# Geiger_Rev1.net
KiCad netlist of a schematic drawn in EAGLE
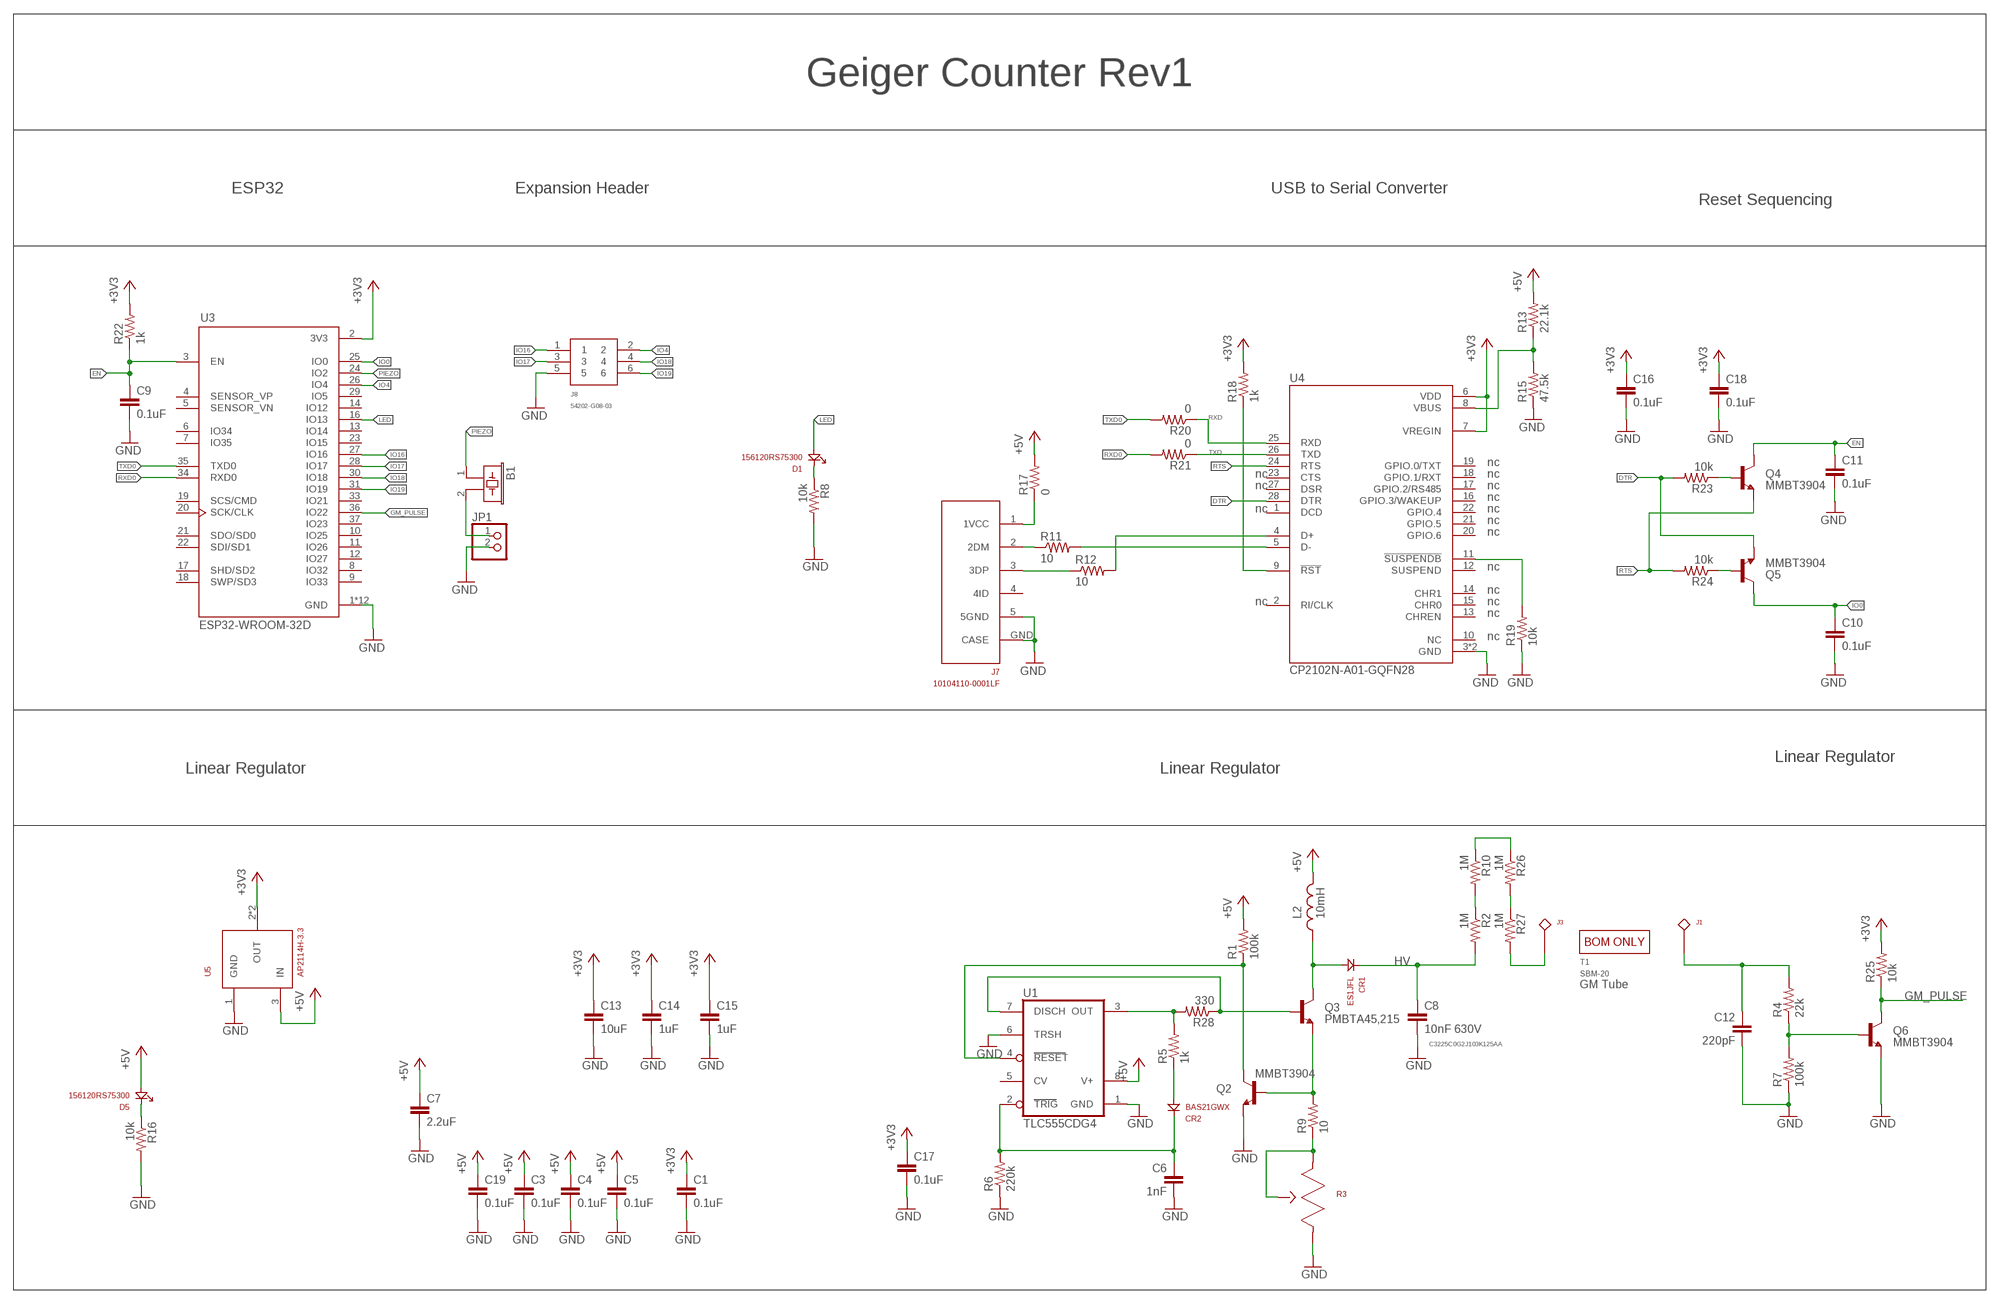
[diagram p0: schematic, sheet 1]

(export (version "E")
  (design (tool "Eeschema 10.0.6"))
  (components
    (comp (ref "B1")
      (value "PIEZO17MM")
      (footprint "eagle-import:PS1740P02E")
      (libsource (lib "eagle-import") (part "PIEZO17MM"))
    )
    (comp (ref "C1")
      (value "0.1uF")
      (footprint "eagle-import:0603")
      (libsource (lib "eagle-import") (part "0603_CAPACITOR"))
    )
    (comp (ref "C3")
      (value "0.1uF")
      (footprint "eagle-import:0603")
      (libsource (lib "eagle-import") (part "0603_CAPACITOR"))
    )
    (comp (ref "C4")
      (value "0.1uF")
      (footprint "eagle-import:0603")
      (libsource (lib "eagle-import") (part "0603_CAPACITOR"))
    )
    (comp (ref "C5")
      (value "0.1uF")
      (footprint "eagle-import:0603")
      (libsource (lib "eagle-import") (part "0603_CAPACITOR"))
    )
    (comp (ref "C6")
      (value "1nF")
      (footprint "eagle-import:0603")
      (libsource (lib "eagle-import") (part "0603_CAPACITOR"))
    )
    (comp (ref "C7")
      (value "2.2uF")
      (footprint "eagle-import:1210")
      (libsource (lib "eagle-import") (part "1210_CAPACITOR"))
    )
    (comp (ref "C8")
      (value "10nF 630V")
      (footprint "eagle-import:1210")
      (libsource (lib "eagle-import") (part "1210_CAPACITOR"))
    )
    (comp (ref "C9")
      (value "0.1uF")
      (footprint "eagle-import:0603")
      (libsource (lib "eagle-import") (part "0603_CAPACITOR"))
    )
    (comp (ref "C10")
      (value "0.1uF")
      (footprint "eagle-import:0603")
      (libsource (lib "eagle-import") (part "0603_CAPACITOR"))
    )
    (comp (ref "C11")
      (value "0.1uF")
      (footprint "eagle-import:0603")
      (libsource (lib "eagle-import") (part "0603_CAPACITOR"))
    )
    (comp (ref "C12")
      (value "220pF")
      (footprint "eagle-import:0603")
      (libsource (lib "eagle-import") (part "0603_CAPACITOR"))
    )
    (comp (ref "C13")
      (value "10uF")
      (footprint "eagle-import:0805")
      (libsource (lib "eagle-import") (part "0805_CAPACITOR"))
    )
    (comp (ref "C14")
      (value "1uF")
      (footprint "eagle-import:0805")
      (libsource (lib "eagle-import") (part "0805_CAPACITOR"))
    )
    (comp (ref "C15")
      (value "1uF")
      (footprint "eagle-import:0805")
      (libsource (lib "eagle-import") (part "0805_CAPACITOR"))
    )
    (comp (ref "C16")
      (value "0.1uF")
      (footprint "eagle-import:0603")
      (libsource (lib "eagle-import") (part "0603_CAPACITOR"))
    )
    (comp (ref "C17")
      (value "0.1uF")
      (footprint "eagle-import:0603")
      (libsource (lib "eagle-import") (part "0603_CAPACITOR"))
    )
    (comp (ref "C18")
      (value "0.1uF")
      (footprint "eagle-import:0603")
      (libsource (lib "eagle-import") (part "0603_CAPACITOR"))
    )
    (comp (ref "C19")
      (value "0.1uF")
      (footprint "eagle-import:0603")
      (libsource (lib "eagle-import") (part "0603_CAPACITOR"))
    )
    (comp (ref "CR1")
      (value "ES1JFL")
      (footprint "eagle-import:SOD123(AK)")
      (fields (field (name "PARTNO") "ES1JFLCT-ND"))
      (libsource (lib "eagle-import") (part "ES1JFL"))
    )
    (comp (ref "CR2")
      (value "BAS21GWX")
      (footprint "eagle-import:SOD123")
      (fields (field (name "PARTNO") "1727-7323-1-ND"))
      (libsource (lib "eagle-import") (part "BAS21GWX"))
    )
    (comp (ref "D1")
      (value "156120RS75300")
      (footprint "eagle-import:1206_REV")
      (fields (field (name "PARTNO") "732-5031-1-ND"))
      (libsource (lib "eagle-import") (part "156120RS75300"))
    )
    (comp (ref "D5")
      (value "156120RS75300")
      (footprint "eagle-import:1206_REV")
      (fields (field (name "PARTNO") "732-5031-1-ND"))
      (libsource (lib "eagle-import") (part "156120RS75300"))
    )
    (comp (ref "J1")
      (value "01010002Z")
      (footprint "eagle-import:01010002Z")
      (fields (field (name "PARTNO") "F4080-ND"))
      (libsource (lib "eagle-import") (part "01010002Z"))
    )
    (comp (ref "J3")
      (value "01010002Z")
      (footprint "eagle-import:01010002Z")
      (fields (field (name "PARTNO") "F4080-ND"))
      (libsource (lib "eagle-import") (part "01010002Z"))
    )
    (comp (ref "J7")
      (value "10104110-0001LF")
      (footprint "eagle-import:MICRO_USB")
      (fields (field (name "PARTNO") "609-4052-1-ND"))
      (libsource (lib "eagle-import") (part "10104110-0001LF"))
    )
    (comp (ref "J8")
      (value "54202-G08-03")
      (footprint "eagle-import:6-SMT-HEADER")
      (fields (field (name "PARTNO") "609-5602-ND"))
      (libsource (lib "eagle-import") (part "54202-G08-03"))
    )
    (comp (ref "JP1")
      (value "PINHD-1X2")
      (footprint "eagle-import:1X02")
      (libsource (lib "eagle-import") (part "PINHD-1X2"))
    )
    (comp (ref "L2")
      (value "10mH")
      (footprint "eagle-import:SDR1005")
      (fields (field (name "PARTNO") "SDR1005-103KLCT-ND"))
      (libsource (lib "eagle-import") (part "SDR1005-103KL"))
    )
    (comp (ref "Q2")
      (value "MMBT3904")
      (footprint "eagle-import:SOT23-3")
      (fields (field (name "PARTNO") "MMBT3904TPMSCT-ND"))
      (libsource (lib "eagle-import") (part "MMBT3904-TP"))
    )
    (comp (ref "Q3")
      (value "PMBTA45,215")
      (footprint "eagle-import:SOT23-3")
      (fields (field (name "PARTNO") "1727-5332-1-ND"))
      (libsource (lib "eagle-import") (part "PMBTA45,215"))
    )
    (comp (ref "Q4")
      (value "MMBT3904")
      (footprint "eagle-import:SOT23-3")
      (fields (field (name "PARTNO") "MMBT3904TPMSCT-ND"))
      (libsource (lib "eagle-import") (part "MMBT3904-TP"))
    )
    (comp (ref "Q5")
      (value "MMBT3904")
      (footprint "eagle-import:SOT23-3")
      (fields (field (name "PARTNO") "MMBT3904TPMSCT-ND"))
      (libsource (lib "eagle-import") (part "MMBT3904-TP"))
    )
    (comp (ref "Q6")
      (value "MMBT3904")
      (footprint "eagle-import:SOT23-3")
      (fields (field (name "PARTNO") "MMBT3904TPMSCT-ND"))
      (libsource (lib "eagle-import") (part "MMBT3904-TP"))
    )
    (comp (ref "R1")
      (value "100k")
      (footprint "eagle-import:0603")
      (libsource (lib "eagle-import") (part "0603_RESISTOR"))
    )
    (comp (ref "R2")
      (value "1M")
      (footprint "eagle-import:0603")
      (libsource (lib "eagle-import") (part "0603_RESISTOR"))
    )
    (comp (ref "R3")
      (value "10")
      (footprint "eagle-import:3361P")
      (fields (field (name "PARTNO") "3361P-1-100GLFCT-ND"))
      (libsource (lib "eagle-import") (part "3361P-1-100GLF"))
    )
    (comp (ref "R4")
      (value "22k")
      (footprint "eagle-import:0603")
      (libsource (lib "eagle-import") (part "0603_RESISTOR"))
    )
    (comp (ref "R5")
      (value "1k")
      (footprint "eagle-import:0603")
      (libsource (lib "eagle-import") (part "0603_RESISTOR"))
    )
    (comp (ref "R6")
      (value "220k")
      (footprint "eagle-import:0603")
      (libsource (lib "eagle-import") (part "0603_RESISTOR"))
    )
    (comp (ref "R7")
      (value "100k")
      (footprint "eagle-import:0603")
      (libsource (lib "eagle-import") (part "0603_RESISTOR"))
    )
    (comp (ref "R8")
      (value "10k")
      (footprint "eagle-import:0603")
      (libsource (lib "eagle-import") (part "0603_RESISTOR"))
    )
    (comp (ref "R9")
      (value "10")
      (footprint "eagle-import:1206")
      (libsource (lib "eagle-import") (part "1206_RESISTOR"))
    )
    (comp (ref "R10")
      (value "1M")
      (footprint "eagle-import:0603")
      (libsource (lib "eagle-import") (part "0603_RESISTOR"))
    )
    (comp (ref "R11")
      (value "10")
      (footprint "eagle-import:0603")
      (libsource (lib "eagle-import") (part "0603_RESISTOR"))
    )
    (comp (ref "R12")
      (value "10")
      (footprint "eagle-import:0603")
      (libsource (lib "eagle-import") (part "0603_RESISTOR"))
    )
    (comp (ref "R13")
      (value "22.1k")
      (footprint "eagle-import:0603")
      (libsource (lib "eagle-import") (part "0603_RESISTOR"))
    )
    (comp (ref "R15")
      (value "47.5k")
      (footprint "eagle-import:0603")
      (libsource (lib "eagle-import") (part "0603_RESISTOR"))
    )
    (comp (ref "R16")
      (value "10k")
      (footprint "eagle-import:0603")
      (libsource (lib "eagle-import") (part "0603_RESISTOR"))
    )
    (comp (ref "R17")
      (value "0")
      (footprint "eagle-import:0603")
      (libsource (lib "eagle-import") (part "0603_RESISTOR"))
    )
    (comp (ref "R18")
      (value "1k")
      (footprint "eagle-import:0603")
      (libsource (lib "eagle-import") (part "0603_RESISTOR"))
    )
    (comp (ref "R19")
      (value "10k")
      (footprint "eagle-import:0603")
      (libsource (lib "eagle-import") (part "0603_RESISTOR"))
    )
    (comp (ref "R20")
      (value "0")
      (footprint "eagle-import:0603")
      (libsource (lib "eagle-import") (part "0603_RESISTOR"))
    )
    (comp (ref "R21")
      (value "0")
      (footprint "eagle-import:0603")
      (libsource (lib "eagle-import") (part "0603_RESISTOR"))
    )
    (comp (ref "R22")
      (value "1k")
      (footprint "eagle-import:0603")
      (libsource (lib "eagle-import") (part "0603_RESISTOR"))
    )
    (comp (ref "R23")
      (value "10k")
      (footprint "eagle-import:0603")
      (libsource (lib "eagle-import") (part "0603_RESISTOR"))
    )
    (comp (ref "R24")
      (value "10k")
      (footprint "eagle-import:0603")
      (libsource (lib "eagle-import") (part "0603_RESISTOR"))
    )
    (comp (ref "R25")
      (value "10k")
      (footprint "eagle-import:0603")
      (libsource (lib "eagle-import") (part "0603_RESISTOR"))
    )
    (comp (ref "R26")
      (value "1M")
      (footprint "eagle-import:0603")
      (libsource (lib "eagle-import") (part "0603_RESISTOR"))
    )
    (comp (ref "R27")
      (value "1M")
      (footprint "eagle-import:0603")
      (libsource (lib "eagle-import") (part "0603_RESISTOR"))
    )
    (comp (ref "R28")
      (value "330")
      (footprint "eagle-import:0603")
      (libsource (lib "eagle-import") (part "0603_RESISTOR"))
    )
    (comp (ref "T1")
      (value "SBM-20")
      (footprint "eagle-import:SBM-20")
      (libsource (lib "eagle-import") (part "SBM-20"))
    )
    (comp (ref "U1")
      (value "TLC555CDG4")
      (footprint "eagle-import:SOIC8")
      (fields (field (name "PARTNO") "296-52992-ND"))
      (libsource (lib "eagle-import") (part "TLC555CDG4"))
    )
    (comp (ref "U3")
      (value "ESP32-WROOM-32D")
      (footprint "eagle-import:MODULE_ESP32-WROOM-32D")
      (fields (field (name "MF") "Espressif Systems"))
      (libsource (lib "eagle-import") (part "ESP32-WROOM-32D"))
    )
    (comp (ref "U4")
      (value "CP2102N-A01-GQFN28")
      (footprint "eagle-import:QFN50P500X500X80-29N")
      (fields (field (name "MF") "Silicon Labs"))
      (libsource (lib "eagle-import") (part "CP2102N-A01-GQFN28"))
    )
    (comp (ref "U5")
      (value "AP2114H-3.3")
      (footprint "eagle-import:SOT223")
      (fields (field (name "PARTNO") "AP2114H-3.3TRG1DICT-ND"))
      (libsource (lib "eagle-import") (part "AP2114H-3.3"))
    )
  )
  (nets
    (net (code "1") (name "+3V3") (class "Default")
      (node (ref "C1") (pin "1") (pinfunction "1_1") (pintype "passive"))
      (node (ref "C13") (pin "1") (pinfunction "1_1") (pintype "passive"))
      (node (ref "C14") (pin "1") (pinfunction "1_1") (pintype "passive"))
      (node (ref "C15") (pin "1") (pinfunction "1_1") (pintype "passive"))
      (node (ref "C16") (pin "1") (pinfunction "1_1") (pintype "passive"))
      (node (ref "C17") (pin "1") (pinfunction "1_1") (pintype "passive"))
      (node (ref "C18") (pin "1") (pinfunction "1_1") (pintype "passive"))
      (node (ref "R18") (pin "2") (pinfunction "2_2") (pintype "passive"))
      (node (ref "R22") (pin "2") (pinfunction "2_2") (pintype "passive"))
      (node (ref "R25") (pin "2") (pinfunction "2_2") (pintype "passive"))
      (node (ref "U3") (pin "2") (pinfunction "3V3_2") (pintype "power_in"))
      (node (ref "U4") (pin "6") (pinfunction "VDD_6") (pintype "power_in"))
      (node (ref "U4") (pin "7") (pinfunction "VREGIN_7") (pintype "power_in"))
      (node (ref "U5") (pin "2") (pinfunction "OUT_2") (pintype "bidirectional"))
      (node (ref "U5") (pin "T") (pinfunction "OUT_T") (pintype "bidirectional"))
    )
    (net (code "2") (name "+5V") (class "Default")
      (node (ref "C19") (pin "1") (pinfunction "1_1") (pintype "passive"))
      (node (ref "C3") (pin "1") (pinfunction "1_1") (pintype "passive"))
      (node (ref "C4") (pin "1") (pinfunction "1_1") (pintype "passive"))
      (node (ref "C5") (pin "1") (pinfunction "1_1") (pintype "passive"))
      (node (ref "C7") (pin "1") (pinfunction "1_1") (pintype "passive"))
      (node (ref "D5") (pin "A") (pinfunction "A_A") (pintype "bidirectional"))
      (node (ref "L2") (pin "P$2") (pinfunction "P$2_P$2") (pintype "bidirectional"))
      (node (ref "R1") (pin "2") (pinfunction "2_2") (pintype "passive"))
      (node (ref "R13") (pin "2") (pinfunction "2_2") (pintype "passive"))
      (node (ref "R17") (pin "2") (pinfunction "2_2") (pintype "passive"))
      (node (ref "U1") (pin "8") (pinfunction "V+_8") (pintype "power_in"))
      (node (ref "U5") (pin "3") (pinfunction "IN_3") (pintype "bidirectional"))
    )
    (net (code "3") (name "/HV") (class "Default")
      (node (ref "C8") (pin "1") (pinfunction "1_1") (pintype "passive"))
      (node (ref "CR1") (pin "K") (pinfunction "K_K") (pintype "bidirectional"))
      (node (ref "R2") (pin "2") (pinfunction "2_2") (pintype "passive"))
    )
    (net (code "4") (name "/RXD") (class "Default")
      (node (ref "R20") (pin "1") (pinfunction "1_1") (pintype "passive"))
      (node (ref "U4") (pin "25") (pinfunction "RXD_25") (pintype "input"))
    )
    (net (code "5") (name "/TXD") (class "Default")
      (node (ref "R21") (pin "1") (pinfunction "1_1") (pintype "passive"))
      (node (ref "U4") (pin "26") (pinfunction "TXD_26") (pintype "output"))
    )
    (net (code "6") (name "DTR") (class "Default")
      (node (ref "Q5") (pin "2") (pinfunction "E_2") (pintype "passive"))
      (node (ref "R23") (pin "2") (pinfunction "2_2") (pintype "passive"))
      (node (ref "U4") (pin "28") (pinfunction "DTR_28") (pintype "output"))
    )
    (net (code "7") (name "EN") (class "Default")
      (node (ref "C11") (pin "1") (pinfunction "1_1") (pintype "passive"))
      (node (ref "C9") (pin "1") (pinfunction "1_1") (pintype "passive"))
      (node (ref "Q4") (pin "3") (pinfunction "C_3") (pintype "passive"))
      (node (ref "R22") (pin "1") (pinfunction "1_1") (pintype "passive"))
      (node (ref "U3") (pin "3") (pinfunction "EN_3") (pintype "input"))
    )
    (net (code "8") (name "GM_PULSE") (class "Default")
      (node (ref "Q6") (pin "3") (pinfunction "C_3") (pintype "passive"))
      (node (ref "R25") (pin "1") (pinfunction "1_1") (pintype "passive"))
      (node (ref "U3") (pin "36") (pinfunction "IO22_36") (pintype "bidirectional"))
    )
    (net (code "9") (name "GND") (class "Default")
      (node (ref "C1") (pin "2") (pinfunction "2_2") (pintype "passive"))
      (node (ref "C10") (pin "2") (pinfunction "2_2") (pintype "passive"))
      (node (ref "C11") (pin "2") (pinfunction "2_2") (pintype "passive"))
      (node (ref "C12") (pin "2") (pinfunction "2_2") (pintype "passive"))
      (node (ref "C13") (pin "2") (pinfunction "2_2") (pintype "passive"))
      (node (ref "C14") (pin "2") (pinfunction "2_2") (pintype "passive"))
      (node (ref "C15") (pin "2") (pinfunction "2_2") (pintype "passive"))
      (node (ref "C16") (pin "2") (pinfunction "2_2") (pintype "passive"))
      (node (ref "C17") (pin "2") (pinfunction "2_2") (pintype "passive"))
      (node (ref "C18") (pin "2") (pinfunction "2_2") (pintype "passive"))
      (node (ref "C19") (pin "2") (pinfunction "2_2") (pintype "passive"))
      (node (ref "C3") (pin "2") (pinfunction "2_2") (pintype "passive"))
      (node (ref "C4") (pin "2") (pinfunction "2_2") (pintype "passive"))
      (node (ref "C5") (pin "2") (pinfunction "2_2") (pintype "passive"))
      (node (ref "C6") (pin "2") (pinfunction "2_2") (pintype "passive"))
      (node (ref "C7") (pin "2") (pinfunction "2_2") (pintype "passive"))
      (node (ref "C8") (pin "2") (pinfunction "2_2") (pintype "passive"))
      (node (ref "C9") (pin "2") (pinfunction "2_2") (pintype "passive"))
      (node (ref "J7") (pin "5") (pinfunction "5GND_5") (pintype "bidirectional"))
      (node (ref "J7") (pin "GND") (pinfunction "CASE_GND") (pintype "bidirectional"))
      (node (ref "J8") (pin "5") (pinfunction "5_5") (pintype "bidirectional"))
      (node (ref "JP1") (pin "2") (pinfunction "2_2") (pintype "passive"))
      (node (ref "Q2") (pin "2") (pinfunction "E_2") (pintype "passive"))
      (node (ref "Q6") (pin "2") (pinfunction "E_2") (pintype "passive"))
      (node (ref "R15") (pin "1") (pinfunction "1_1") (pintype "passive"))
      (node (ref "R16") (pin "2") (pinfunction "2_2") (pintype "passive"))
      (node (ref "R19") (pin "1") (pinfunction "1_1") (pintype "passive"))
      (node (ref "R3") (pin "3") (pinfunction "3_3") (pintype "bidirectional"))
      (node (ref "R6") (pin "1") (pinfunction "1_1") (pintype "passive"))
      (node (ref "R7") (pin "1") (pinfunction "1_1") (pintype "passive"))
      (node (ref "R8") (pin "2") (pinfunction "2_2") (pintype "passive"))
      (node (ref "U1") (pin "1") (pinfunction "GND_1") (pintype "power_in"))
      (node (ref "U1") (pin "6") (pinfunction "TRSH_6") (pintype "input"))
      (node (ref "U3") (pin "1") (pinfunction "GND_1") (pintype "power_in"))
      (node (ref "U3") (pin "15") (pinfunction "GND_15") (pintype "power_in"))
      (node (ref "U3") (pin "38") (pinfunction "GND_38") (pintype "power_in"))
      (node (ref "U3") (pin "39_1") (pinfunction "GND_39_1") (pintype "power_in"))
      (node (ref "U3") (pin "39_2") (pinfunction "GND_39_2") (pintype "power_in"))
      (node (ref "U3") (pin "39_3") (pinfunction "GND_39_3") (pintype "power_in"))
      (node (ref "U3") (pin "39_4") (pinfunction "GND_39_4") (pintype "power_in"))
      (node (ref "U3") (pin "39_5") (pinfunction "GND_39_5") (pintype "power_in"))
      (node (ref "U3") (pin "39_6") (pinfunction "GND_39_6") (pintype "power_in"))
      (node (ref "U3") (pin "39_7") (pinfunction "GND_39_7") (pintype "power_in"))
      (node (ref "U3") (pin "39_8") (pinfunction "GND_39_8") (pintype "power_in"))
      (node (ref "U3") (pin "39_9") (pinfunction "GND_39_9") (pintype "power_in"))
      (node (ref "U4") (pin "29") (pinfunction "GND_29") (pintype "power_in"))
      (node (ref "U4") (pin "3") (pinfunction "GND_3") (pintype "power_in"))
      (node (ref "U5") (pin "1") (pinfunction "GND_1") (pintype "bidirectional"))
    )
    (net (code "10") (name "IO0") (class "Default")
      (node (ref "C10") (pin "1") (pinfunction "1_1") (pintype "passive"))
      (node (ref "Q5") (pin "3") (pinfunction "C_3") (pintype "passive"))
      (node (ref "U3") (pin "25") (pinfunction "IO0_25") (pintype "bidirectional"))
    )
    (net (code "11") (name "IO4") (class "Default")
      (node (ref "J8") (pin "2") (pinfunction "2_2") (pintype "bidirectional"))
      (node (ref "U3") (pin "26") (pinfunction "IO4_26") (pintype "bidirectional"))
    )
    (net (code "12") (name "IO16") (class "Default")
      (node (ref "J8") (pin "1") (pinfunction "1_1") (pintype "bidirectional"))
      (node (ref "U3") (pin "27") (pinfunction "IO16_27") (pintype "bidirectional"))
    )
    (net (code "13") (name "IO17") (class "Default")
      (node (ref "J8") (pin "3") (pinfunction "3_3") (pintype "bidirectional"))
      (node (ref "U3") (pin "28") (pinfunction "IO17_28") (pintype "bidirectional"))
    )
    (net (code "14") (name "IO18") (class "Default")
      (node (ref "J8") (pin "4") (pinfunction "4_4") (pintype "bidirectional"))
      (node (ref "U3") (pin "30") (pinfunction "IO18_30") (pintype "bidirectional"))
    )
    (net (code "15") (name "IO19") (class "Default")
      (node (ref "J8") (pin "6") (pinfunction "6_6") (pintype "bidirectional"))
      (node (ref "U3") (pin "31") (pinfunction "IO19_31") (pintype "bidirectional"))
    )
    (net (code "16") (name "LED") (class "Default")
      (node (ref "D1") (pin "A") (pinfunction "A_A") (pintype "bidirectional"))
      (node (ref "U3") (pin "16") (pinfunction "IO13_16") (pintype "bidirectional"))
    )
    (net (code "17") (name "Net-(B1-Pad2)") (class "Default")
      (node (ref "B1") (pin "2") (pinfunction "2_2") (pintype "passive"))
      (node (ref "JP1") (pin "1") (pinfunction "1_1") (pintype "passive"))
    )
    (net (code "18") (name "Net-(C12-Pad1)") (class "Default")
      (node (ref "C12") (pin "1") (pinfunction "1_1") (pintype "passive"))
      (node (ref "J1") (pin "P$1") (pinfunction "P$1_P$1") (pintype "bidirectional"))
      (node (ref "R4") (pin "2") (pinfunction "2_2") (pintype "passive"))
    )
    (net (code "19") (name "Net-(CR2-A)") (class "Default")
      (node (ref "CR2") (pin "2") (pinfunction "A_2") (pintype "bidirectional"))
      (node (ref "R5") (pin "1") (pinfunction "1_1") (pintype "passive"))
    )
    (net (code "20") (name "Net-(CR2-K)") (class "Default")
      (node (ref "C6") (pin "1") (pinfunction "1_1") (pintype "passive"))
      (node (ref "CR2") (pin "1") (pinfunction "K_1") (pintype "bidirectional"))
      (node (ref "R6") (pin "2") (pinfunction "2_2") (pintype "passive"))
      (node (ref "U1") (pin "2") (pinfunction "TRIG_2") (pintype "bidirectional"))
    )
    (net (code "21") (name "Net-(D1-PadK)") (class "Default")
      (node (ref "D1") (pin "K") (pinfunction "K_K") (pintype "bidirectional"))
      (node (ref "R8") (pin "1") (pinfunction "1_1") (pintype "passive"))
    )
    (net (code "22") (name "Net-(D5-PadK)") (class "Default")
      (node (ref "D5") (pin "K") (pinfunction "K_K") (pintype "bidirectional"))
      (node (ref "R16") (pin "1") (pinfunction "1_1") (pintype "passive"))
    )
    (net (code "23") (name "Net-(J3-PadP$1)") (class "Default")
      (node (ref "J3") (pin "P$1") (pinfunction "P$1_P$1") (pintype "bidirectional"))
      (node (ref "R27") (pin "2") (pinfunction "2_2") (pintype "passive"))
    )
    (net (code "24") (name "Net-(J7-1VCC)") (class "Default")
      (node (ref "J7") (pin "1") (pinfunction "1VCC_1") (pintype "bidirectional"))
      (node (ref "R17") (pin "1") (pinfunction "1_1") (pintype "passive"))
    )
    (net (code "25") (name "Net-(J7-2DM)") (class "Default")
      (node (ref "J7") (pin "2") (pinfunction "2DM_2") (pintype "bidirectional"))
      (node (ref "R11") (pin "1") (pinfunction "1_1") (pintype "passive"))
    )
    (net (code "26") (name "Net-(J7-3DP)") (class "Default")
      (node (ref "J7") (pin "3") (pinfunction "3DP_3") (pintype "bidirectional"))
      (node (ref "R12") (pin "1") (pinfunction "1_1") (pintype "passive"))
    )
    (net (code "27") (name "Net-(Q2-B)") (class "Default")
      (node (ref "Q2") (pin "1") (pinfunction "B_1") (pintype "passive"))
      (node (ref "Q3") (pin "2") (pinfunction "E_2") (pintype "passive"))
      (node (ref "R9") (pin "2") (pinfunction "2_2") (pintype "passive"))
    )
    (net (code "28") (name "Net-(Q2-C)") (class "Default")
      (node (ref "Q2") (pin "3") (pinfunction "C_3") (pintype "passive"))
      (node (ref "R1") (pin "1") (pinfunction "1_1") (pintype "passive"))
      (node (ref "U1") (pin "4") (pinfunction "RESET_4") (pintype "input"))
    )
    (net (code "29") (name "Net-(Q3-B)") (class "Default")
      (node (ref "Q3") (pin "1") (pinfunction "B_1") (pintype "passive"))
      (node (ref "R28") (pin "1") (pinfunction "1_1") (pintype "passive"))
      (node (ref "U1") (pin "7") (pinfunction "DISCH_7") (pintype "input"))
    )
    (net (code "30") (name "Net-(Q3-C)") (class "Default")
      (node (ref "CR1") (pin "A") (pinfunction "A_A") (pintype "bidirectional"))
      (node (ref "L2") (pin "P$1") (pinfunction "P$1_P$1") (pintype "bidirectional"))
      (node (ref "Q3") (pin "3") (pinfunction "C_3") (pintype "passive"))
    )
    (net (code "31") (name "Net-(Q4-B)") (class "Default")
      (node (ref "Q4") (pin "1") (pinfunction "B_1") (pintype "passive"))
      (node (ref "R23") (pin "1") (pinfunction "1_1") (pintype "passive"))
    )
    (net (code "32") (name "Net-(Q5-B)") (class "Default")
      (node (ref "Q5") (pin "1") (pinfunction "B_1") (pintype "passive"))
      (node (ref "R24") (pin "1") (pinfunction "1_1") (pintype "passive"))
    )
    (net (code "33") (name "Net-(Q6-B)") (class "Default")
      (node (ref "Q6") (pin "1") (pinfunction "B_1") (pintype "passive"))
      (node (ref "R4") (pin "1") (pinfunction "1_1") (pintype "passive"))
      (node (ref "R7") (pin "2") (pinfunction "2_2") (pintype "passive"))
    )
    (net (code "34") (name "Net-(R3-Pad1)") (class "Default")
      (node (ref "R3") (pin "1") (pinfunction "1_1") (pintype "bidirectional"))
      (node (ref "R3") (pin "2") (pinfunction "2_2") (pintype "bidirectional"))
      (node (ref "R9") (pin "1") (pinfunction "1_1") (pintype "passive"))
    )
    (net (code "35") (name "Net-(R10-Pad1)") (class "Default")
      (node (ref "R10") (pin "1") (pinfunction "1_1") (pintype "passive"))
      (node (ref "R26") (pin "1") (pinfunction "1_1") (pintype "passive"))
    )
    (net (code "36") (name "Net-(R10-Pad2)") (class "Default")
      (node (ref "R10") (pin "2") (pinfunction "2_2") (pintype "passive"))
      (node (ref "R2") (pin "1") (pinfunction "1_1") (pintype "passive"))
    )
    (net (code "37") (name "Net-(R26-Pad2)") (class "Default")
      (node (ref "R26") (pin "2") (pinfunction "2_2") (pintype "passive"))
      (node (ref "R27") (pin "1") (pinfunction "1_1") (pintype "passive"))
    )
    (net (code "38") (name "Net-(U1-OUT)") (class "Default")
      (node (ref "R28") (pin "2") (pinfunction "2_2") (pintype "passive"))
      (node (ref "R5") (pin "2") (pinfunction "2_2") (pintype "passive"))
      (node (ref "U1") (pin "3") (pinfunction "OUT_3") (pintype "output"))
    )
    (net (code "39") (name "Net-(U4-D+)") (class "Default")
      (node (ref "R12") (pin "2") (pinfunction "2_2") (pintype "passive"))
      (node (ref "U4") (pin "4") (pinfunction "D+_4") (pintype "bidirectional"))
    )
    (net (code "40") (name "Net-(U4-D-)") (class "Default")
      (node (ref "R11") (pin "2") (pinfunction "2_2") (pintype "passive"))
      (node (ref "U4") (pin "5") (pinfunction "D-_5") (pintype "bidirectional"))
    )
    (net (code "41") (name "Net-(U4-VBUS)") (class "Default")
      (node (ref "R13") (pin "1") (pinfunction "1_1") (pintype "passive"))
      (node (ref "R15") (pin "2") (pinfunction "2_2") (pintype "passive"))
      (node (ref "U4") (pin "8") (pinfunction "VBUS_8") (pintype "power_in"))
    )
    (net (code "42") (name "Net-(U4-~{RST})") (class "Default")
      (node (ref "R18") (pin "1") (pinfunction "1_1") (pintype "passive"))
      (node (ref "U4") (pin "9") (pinfunction "~{RST}_9") (pintype "input"))
    )
    (net (code "43") (name "Net-(U4-~{SUSPENDB})") (class "Default")
      (node (ref "R19") (pin "2") (pinfunction "2_2") (pintype "passive"))
      (node (ref "U4") (pin "11") (pinfunction "~{SUSPENDB}_11") (pintype "output"))
    )
    (net (code "44") (name "PIEZO") (class "Default")
      (node (ref "B1") (pin "1") (pinfunction "1_1") (pintype "passive"))
      (node (ref "U3") (pin "24") (pinfunction "IO2_24") (pintype "bidirectional"))
    )
    (net (code "45") (name "RTS") (class "Default")
      (node (ref "Q4") (pin "2") (pinfunction "E_2") (pintype "passive"))
      (node (ref "R24") (pin "2") (pinfunction "2_2") (pintype "passive"))
      (node (ref "U4") (pin "24") (pinfunction "RTS_24") (pintype "output"))
    )
    (net (code "46") (name "RXD0") (class "Default")
      (node (ref "R21") (pin "2") (pinfunction "2_2") (pintype "passive"))
      (node (ref "U3") (pin "34") (pinfunction "RXD0_34") (pintype "bidirectional"))
    )
    (net (code "47") (name "TXD0") (class "Default")
      (node (ref "R20") (pin "2") (pinfunction "2_2") (pintype "passive"))
      (node (ref "U3") (pin "35") (pinfunction "TXD0_35") (pintype "bidirectional"))
    )
    (net (code "48") (name "unconnected-(J7-4ID-Pad4)") (class "Default")
      (node (ref "J7") (pin "4") (pinfunction "4ID_4") (pintype "bidirectional"))
    )
    (net (code "49") (name "unconnected-(U1-CV-Pad5)") (class "Default")
      (node (ref "U1") (pin "5") (pinfunction "CV_5") (pintype "passive"))
    )
    (net (code "50") (name "unconnected-(U3-IO5-Pad29)") (class "Default")
      (node (ref "U3") (pin "29") (pinfunction "IO5_29") (pintype "bidirectional"))
    )
    (net (code "51") (name "unconnected-(U3-IO12-Pad14)") (class "Default")
      (node (ref "U3") (pin "14") (pinfunction "IO12_14") (pintype "bidirectional"))
    )
    (net (code "52") (name "unconnected-(U3-IO14-Pad13)") (class "Default")
      (node (ref "U3") (pin "13") (pinfunction "IO14_13") (pintype "bidirectional"))
    )
    (net (code "53") (name "unconnected-(U3-IO15-Pad23)") (class "Default")
      (node (ref "U3") (pin "23") (pinfunction "IO15_23") (pintype "bidirectional"))
    )
    (net (code "54") (name "unconnected-(U3-IO21-Pad33)") (class "Default")
      (node (ref "U3") (pin "33") (pinfunction "IO21_33") (pintype "bidirectional"))
    )
    (net (code "55") (name "unconnected-(U3-IO23-Pad37)") (class "Default")
      (node (ref "U3") (pin "37") (pinfunction "IO23_37") (pintype "bidirectional"))
    )
    (net (code "56") (name "unconnected-(U3-IO25-Pad10)") (class "Default")
      (node (ref "U3") (pin "10") (pinfunction "IO25_10") (pintype "bidirectional"))
    )
    (net (code "57") (name "unconnected-(U3-IO26-Pad11)") (class "Default")
      (node (ref "U3") (pin "11") (pinfunction "IO26_11") (pintype "bidirectional"))
    )
    (net (code "58") (name "unconnected-(U3-IO27-Pad12)") (class "Default")
      (node (ref "U3") (pin "12") (pinfunction "IO27_12") (pintype "bidirectional"))
    )
    (net (code "59") (name "unconnected-(U3-IO32-Pad8)") (class "Default")
      (node (ref "U3") (pin "8") (pinfunction "IO32_8") (pintype "bidirectional"))
    )
    (net (code "60") (name "unconnected-(U3-IO33-Pad9)") (class "Default")
      (node (ref "U3") (pin "9") (pinfunction "IO33_9") (pintype "bidirectional"))
    )
    (net (code "61") (name "unconnected-(U3-IO34-Pad6)") (class "Default")
      (node (ref "U3") (pin "6") (pinfunction "IO34_6") (pintype "input"))
    )
    (net (code "62") (name "unconnected-(U3-IO35-Pad7)") (class "Default")
      (node (ref "U3") (pin "7") (pinfunction "IO35_7") (pintype "input"))
    )
    (net (code "63") (name "unconnected-(U3-SCK{slash}CLK-Pad20)") (class "Default")
      (node (ref "U3") (pin "20") (pinfunction "SCK/CLK_20") (pintype "bidirectional"))
    )
    (net (code "64") (name "unconnected-(U3-SCS{slash}CMD-Pad19)") (class "Default")
      (node (ref "U3") (pin "19") (pinfunction "SCS/CMD_19") (pintype "bidirectional"))
    )
    (net (code "65") (name "unconnected-(U3-SDI{slash}SD1-Pad22)") (class "Default")
      (node (ref "U3") (pin "22") (pinfunction "SDI/SD1_22") (pintype "bidirectional"))
    )
    (net (code "66") (name "unconnected-(U3-SDO{slash}SD0-Pad21)") (class "Default")
      (node (ref "U3") (pin "21") (pinfunction "SDO/SD0_21") (pintype "bidirectional"))
    )
    (net (code "67") (name "unconnected-(U3-SENSOR_VN-Pad5)") (class "Default")
      (node (ref "U3") (pin "5") (pinfunction "SENSOR_VN_5") (pintype "input"))
    )
    (net (code "68") (name "unconnected-(U3-SENSOR_VP-Pad4)") (class "Default")
      (node (ref "U3") (pin "4") (pinfunction "SENSOR_VP_4") (pintype "input"))
    )
    (net (code "69") (name "unconnected-(U3-SHD{slash}SD2-Pad17)") (class "Default")
      (node (ref "U3") (pin "17") (pinfunction "SHD/SD2_17") (pintype "bidirectional"))
    )
    (net (code "70") (name "unconnected-(U3-SWP{slash}SD3-Pad18)") (class "Default")
      (node (ref "U3") (pin "18") (pinfunction "SWP/SD3_18") (pintype "bidirectional"))
    )
    (net (code "71") (name "unconnected-(U4-CHR0-Pad15)") (class "Default")
      (node (ref "U4") (pin "15") (pinfunction "CHR0_15") (pintype "output"))
    )
    (net (code "72") (name "unconnected-(U4-CHR1-Pad14)") (class "Default")
      (node (ref "U4") (pin "14") (pinfunction "CHR1_14") (pintype "output"))
    )
    (net (code "73") (name "unconnected-(U4-CHREN-Pad13)") (class "Default")
      (node (ref "U4") (pin "13") (pinfunction "CHREN_13") (pintype "output"))
    )
    (net (code "74") (name "unconnected-(U4-CTS-Pad23)") (class "Default")
      (node (ref "U4") (pin "23") (pinfunction "CTS_23") (pintype "input"))
    )
    (net (code "75") (name "unconnected-(U4-DCD-Pad1)") (class "Default")
      (node (ref "U4") (pin "1") (pinfunction "DCD_1") (pintype "input"))
    )
    (net (code "76") (name "unconnected-(U4-DSR-Pad27)") (class "Default")
      (node (ref "U4") (pin "27") (pinfunction "DSR_27") (pintype "input"))
    )
    (net (code "77") (name "unconnected-(U4-GPIO.0{slash}TXT-Pad19)") (class "Default")
      (node (ref "U4") (pin "19") (pinfunction "GPIO.0/TXT_19") (pintype "bidirectional"))
    )
    (net (code "78") (name "unconnected-(U4-GPIO.1{slash}RXT-Pad18)") (class "Default")
      (node (ref "U4") (pin "18") (pinfunction "GPIO.1/RXT_18") (pintype "bidirectional"))
    )
    (net (code "79") (name "unconnected-(U4-GPIO.2{slash}RS485-Pad17)") (class "Default")
      (node (ref "U4") (pin "17") (pinfunction "GPIO.2/RS485_17") (pintype "bidirectional"))
    )
    (net (code "80") (name "unconnected-(U4-GPIO.3{slash}WAKEUP-Pad16)") (class "Default")
      (node (ref "U4") (pin "16") (pinfunction "GPIO.3/WAKEUP_16") (pintype "bidirectional"))
    )
    (net (code "81") (name "unconnected-(U4-GPIO.4-Pad22)") (class "Default")
      (node (ref "U4") (pin "22") (pinfunction "GPIO.4_22") (pintype "bidirectional"))
    )
    (net (code "82") (name "unconnected-(U4-GPIO.5-Pad21)") (class "Default")
      (node (ref "U4") (pin "21") (pinfunction "GPIO.5_21") (pintype "bidirectional"))
    )
    (net (code "83") (name "unconnected-(U4-GPIO.6-Pad20)") (class "Default")
      (node (ref "U4") (pin "20") (pinfunction "GPIO.6_20") (pintype "bidirectional"))
    )
    (net (code "84") (name "unconnected-(U4-NC-Pad10)") (class "Default")
      (node (ref "U4") (pin "10") (pinfunction "NC_10") (pintype "no_connect"))
    )
    (net (code "85") (name "unconnected-(U4-RI{slash}CLK-Pad2)") (class "Default")
      (node (ref "U4") (pin "2") (pinfunction "RI/CLK_2") (pintype "bidirectional"))
    )
    (net (code "86") (name "unconnected-(U4-SUSPEND-Pad12)") (class "Default")
      (node (ref "U4") (pin "12") (pinfunction "SUSPEND_12") (pintype "output"))
    )
  )
)
